# SparkFun_Qwiic_CO2_Sensor_SCD40.net
KiCad netlist of a schematic drawn in EAGLE
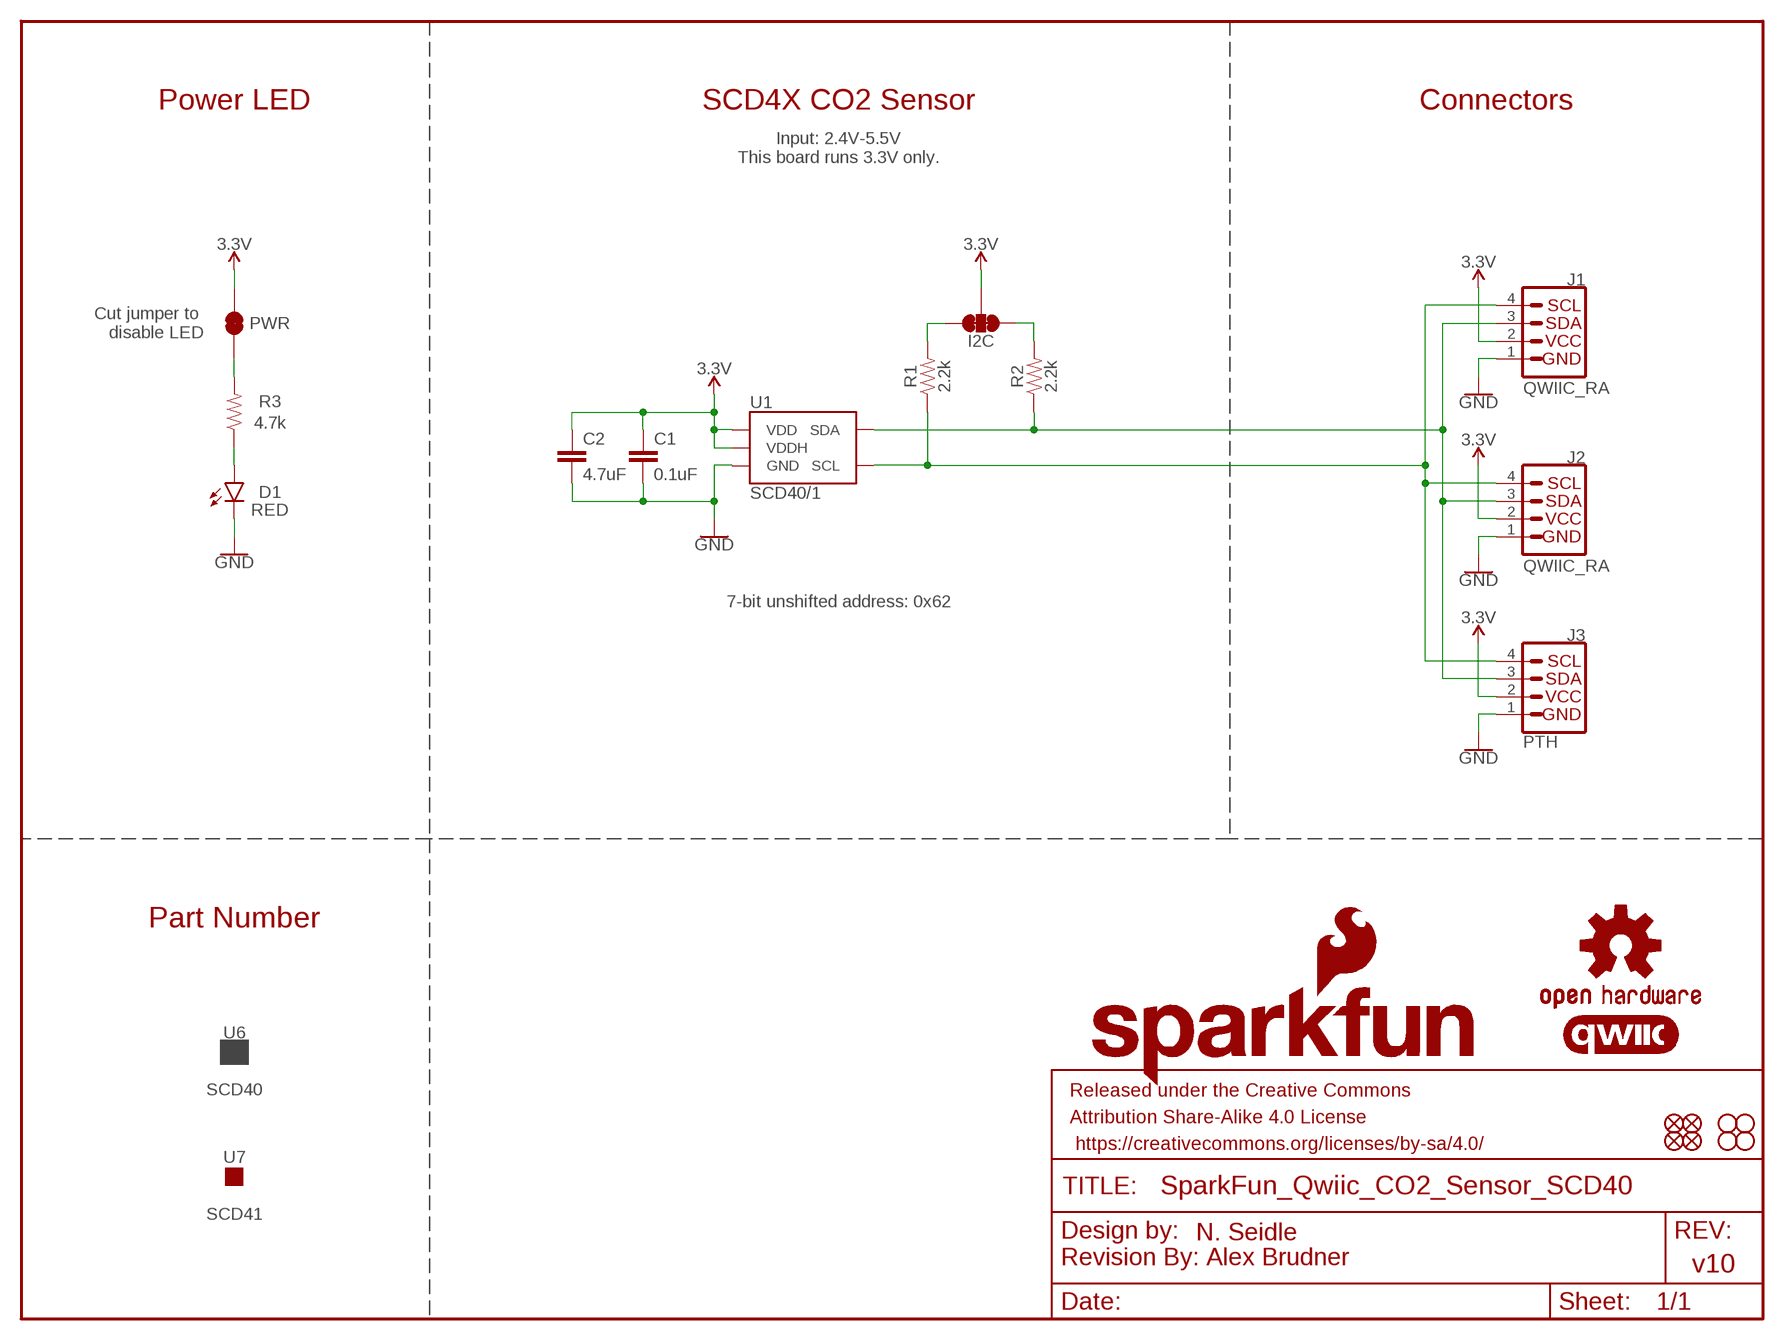
[diagram p0: schematic, sheet 1]

(export (version "E")
  (design (tool "Eeschema 10.0.6"))
  (components
    (comp (ref "C1")
      (value "0.1uF")
      (footprint "eagle-import:0603")
      (libsource (lib "eagle-import") (part "0.1UF-0603-25V-10%-X7R-WE"))
    )
    (comp (ref "C2")
      (value "4.7uF")
      (footprint "eagle-import:0603")
      (libsource (lib "eagle-import") (part "4.7UF-0603-6.3V-(10%)"))
    )
    (comp (ref "D1")
      (value "RED")
      (footprint "eagle-import:LED-0603")
      (libsource (lib "eagle-import") (part "LED-RED_0603-KB"))
    )
    (comp (ref "FD1")
      (value "FIDUCIALUFIDUCIAL")
      (footprint "eagle-import:FIDUCIAL-MICRO")
      (libsource (lib "eagle-import") (part "FIDUCIALUFIDUCIAL"))
    )
    (comp (ref "FD2")
      (value "FIDUCIALUFIDUCIAL")
      (footprint "eagle-import:FIDUCIAL-MICRO")
      (libsource (lib "eagle-import") (part "FIDUCIALUFIDUCIAL"))
    )
    (comp (ref "FD3")
      (value "FIDUCIALUFIDUCIAL")
      (footprint "eagle-import:FIDUCIAL-MICRO")
      (libsource (lib "eagle-import") (part "FIDUCIALUFIDUCIAL"))
    )
    (comp (ref "FD4")
      (value "FIDUCIALUFIDUCIAL")
      (footprint "eagle-import:FIDUCIAL-MICRO")
      (libsource (lib "eagle-import") (part "FIDUCIALUFIDUCIAL"))
    )
    (comp (ref "FRAME1")
      (value "FRAME-LETTER")
      (footprint "eagle-import:CREATIVE_COMMONS")
      (fields
        (field (name "BASEDON") "Revision By: Alex Brudner")
        (field (name "DESIGNER") "N. Seidle")
        (field (name "REV") "v10")
      )
      (libsource (lib "eagle-import") (part "FRAME-LETTER"))
    )
    (comp (ref "H1")
      (value "STAND-OFF")
      (footprint "eagle-import:STAND-OFF")
      (libsource (lib "eagle-import") (part "STAND-OFF"))
    )
    (comp (ref "H2")
      (value "STAND-OFF")
      (footprint "eagle-import:STAND-OFF")
      (libsource (lib "eagle-import") (part "STAND-OFF"))
    )
    (comp (ref "H3")
      (value "STAND-OFF")
      (footprint "eagle-import:STAND-OFF")
      (libsource (lib "eagle-import") (part "STAND-OFF"))
    )
    (comp (ref "H4")
      (value "STAND-OFF")
      (footprint "eagle-import:STAND-OFF")
      (libsource (lib "eagle-import") (part "STAND-OFF"))
    )
    (comp (ref "I2C")
      (value "I2C")
      (footprint "eagle-import:SMT-JUMPER_3_2-NC_TRACE_SILK")
      (libsource (lib "eagle-import") (part "JUMPER-SMT_3_2-NC_TRACE_SILK"))
    )
    (comp (ref "J1")
      (value "QWIIC_RA")
      (footprint "eagle-import:JST04_1MM_RA")
      (libsource (lib "eagle-import") (part "QWIIC_CONNECTORJS-1MM"))
    )
    (comp (ref "J2")
      (value "QWIIC_RA")
      (footprint "eagle-import:JST04_1MM_RA")
      (libsource (lib "eagle-import") (part "QWIIC_CONNECTORJS-1MM"))
    )
    (comp (ref "J3")
      (value "PTH")
      (footprint "eagle-import:1X04_NO_SILK")
      (libsource (lib "eagle-import") (part "I2C_STANDARD_NO_SILK"))
    )
    (comp (ref "LOGO1")
      (value "QWIIC_LOGO_CONNECTOR")
      (footprint "eagle-import:QWIIC_5.5MM")
      (libsource (lib "eagle-import") (part "QWIIC_LOGO_CONNECTOR"))
    )
    (comp (ref "LOGO2")
      (value "OSHW-LOGOS")
      (footprint "eagle-import:OSHW-LOGO-S")
      (libsource (lib "eagle-import") (part "OSHW-LOGOS"))
    )
    (comp (ref "LOGO3")
      (value "SFE_LOGO_NAME_FLAMEBLANK")
      (footprint "eagle-import:BLANK")
      (libsource (lib "eagle-import") (part "SFE_LOGO_NAME_FLAMEBLANK"))
    )
    (comp (ref "PWR")
      (value "PWR")
      (footprint "eagle-import:SMT-JUMPER_2_NC_TRACE_SILK")
      (libsource (lib "eagle-import") (part "JUMPER-SMT_2_NC_TRACE_SILK"))
    )
    (comp (ref "R1")
      (value "2.2k")
      (footprint "eagle-import:0603")
      (libsource (lib "eagle-import") (part "2.2KOHM-0603-1/10W-1%"))
    )
    (comp (ref "R2")
      (value "2.2k")
      (footprint "eagle-import:0603")
      (libsource (lib "eagle-import") (part "2.2KOHM-0603-1/10W-1%"))
    )
    (comp (ref "R3")
      (value "4.7k")
      (footprint "eagle-import:0603")
      (libsource (lib "eagle-import") (part "4.7KOHM-0603-1/10W-1%"))
    )
    (comp (ref "U1")
      (value "SCD40/1")
      (footprint "eagle-import:SCD4X")
      (libsource (lib "eagle-import") (part "SCD4X"))
    )
    (comp (ref "U6")
      (value "SCD40")
      (footprint "eagle-import:PRODUCT_IDENT_PASTE_NO-SILK")
      (libsource (lib "eagle-import") (part "PROD_ID_PASTE_NO-SILK"))
    )
    (comp (ref "U7")
      (value "SCD41")
      (footprint "eagle-import:PRODUCT_IDENT_NO_NO-SILK")
      (libsource (lib "eagle-import") (part "PROD_ID_NO-PASTE_NO_SILK"))
    )
  )
  (nets
    (net (code "1") (name "3.3V") (class "Default")
      (node (ref "C1") (pin "1") (pinfunction "1_1") (pintype "passive"))
      (node (ref "C2") (pin "1") (pinfunction "1_1") (pintype "passive"))
      (node (ref "I2C") (pin "2") (pinfunction "2_2") (pintype "passive"))
      (node (ref "J1") (pin "2") (pinfunction "2_2") (pintype "power_in"))
      (node (ref "J2") (pin "2") (pinfunction "2_2") (pintype "power_in"))
      (node (ref "J3") (pin "2") (pinfunction "2_2") (pintype "power_in"))
      (node (ref "PWR") (pin "2") (pinfunction "2_2") (pintype "passive"))
      (node (ref "U1") (pin "19") (pinfunction "VDDH_19") (pintype "power_in"))
      (node (ref "U1") (pin "7") (pinfunction "VDD_7") (pintype "power_in"))
    )
    (net (code "2") (name "GND") (class "Default")
      (node (ref "C1") (pin "2") (pinfunction "2_2") (pintype "passive"))
      (node (ref "C2") (pin "2") (pinfunction "2_2") (pintype "passive"))
      (node (ref "D1") (pin "C") (pinfunction "C_C") (pintype "passive"))
      (node (ref "J1") (pin "1") (pinfunction "1_1") (pintype "power_in"))
      (node (ref "J2") (pin "1") (pinfunction "1_1") (pintype "power_in"))
      (node (ref "J3") (pin "1") (pinfunction "1_1") (pintype "power_in"))
      (node (ref "U1") (pin "20") (pinfunction "GND_20") (pintype "power_in"))
      (node (ref "U1") (pin "6") (pinfunction "GND_6") (pintype "power_in"))
      (node (ref "U1") (pin "CP") (pinfunction "GND_CP") (pintype "power_in"))
    )
    (net (code "3") (name "Net-(D1-PadA)") (class "Default")
      (node (ref "D1") (pin "A") (pinfunction "A_A") (pintype "passive"))
      (node (ref "R3") (pin "1") (pinfunction "1_1") (pintype "passive"))
    )
    (net (code "4") (name "Net-(I2C-Pad1)") (class "Default")
      (node (ref "I2C") (pin "1") (pinfunction "1_1") (pintype "passive"))
      (node (ref "R2") (pin "2") (pinfunction "2_2") (pintype "passive"))
    )
    (net (code "5") (name "Net-(I2C-Pad3)") (class "Default")
      (node (ref "I2C") (pin "3") (pinfunction "3_3") (pintype "passive"))
      (node (ref "R1") (pin "2") (pinfunction "2_2") (pintype "passive"))
    )
    (net (code "6") (name "Net-(PWR-Pad1)") (class "Default")
      (node (ref "PWR") (pin "1") (pinfunction "1_1") (pintype "passive"))
      (node (ref "R3") (pin "2") (pinfunction "2_2") (pintype "passive"))
    )
    (net (code "7") (name "Net-(U1-SCL)") (class "Default")
      (node (ref "J1") (pin "4") (pinfunction "4_4") (pintype "passive"))
      (node (ref "J2") (pin "4") (pinfunction "4_4") (pintype "passive"))
      (node (ref "J3") (pin "4") (pinfunction "4_4") (pintype "passive"))
      (node (ref "R1") (pin "1") (pinfunction "1_1") (pintype "passive"))
      (node (ref "U1") (pin "9") (pinfunction "SCL_9") (pintype "bidirectional"))
    )
    (net (code "8") (name "Net-(U1-SDA)") (class "Default")
      (node (ref "J1") (pin "3") (pinfunction "3_3") (pintype "passive"))
      (node (ref "J2") (pin "3") (pinfunction "3_3") (pintype "passive"))
      (node (ref "J3") (pin "3") (pinfunction "3_3") (pintype "passive"))
      (node (ref "R2") (pin "1") (pinfunction "1_1") (pintype "passive"))
      (node (ref "U1") (pin "10") (pinfunction "SDA_10") (pintype "bidirectional"))
    )
  )
)
